# adapter-cast.net
KiCad netlist of a schematic drawn in EAGLE
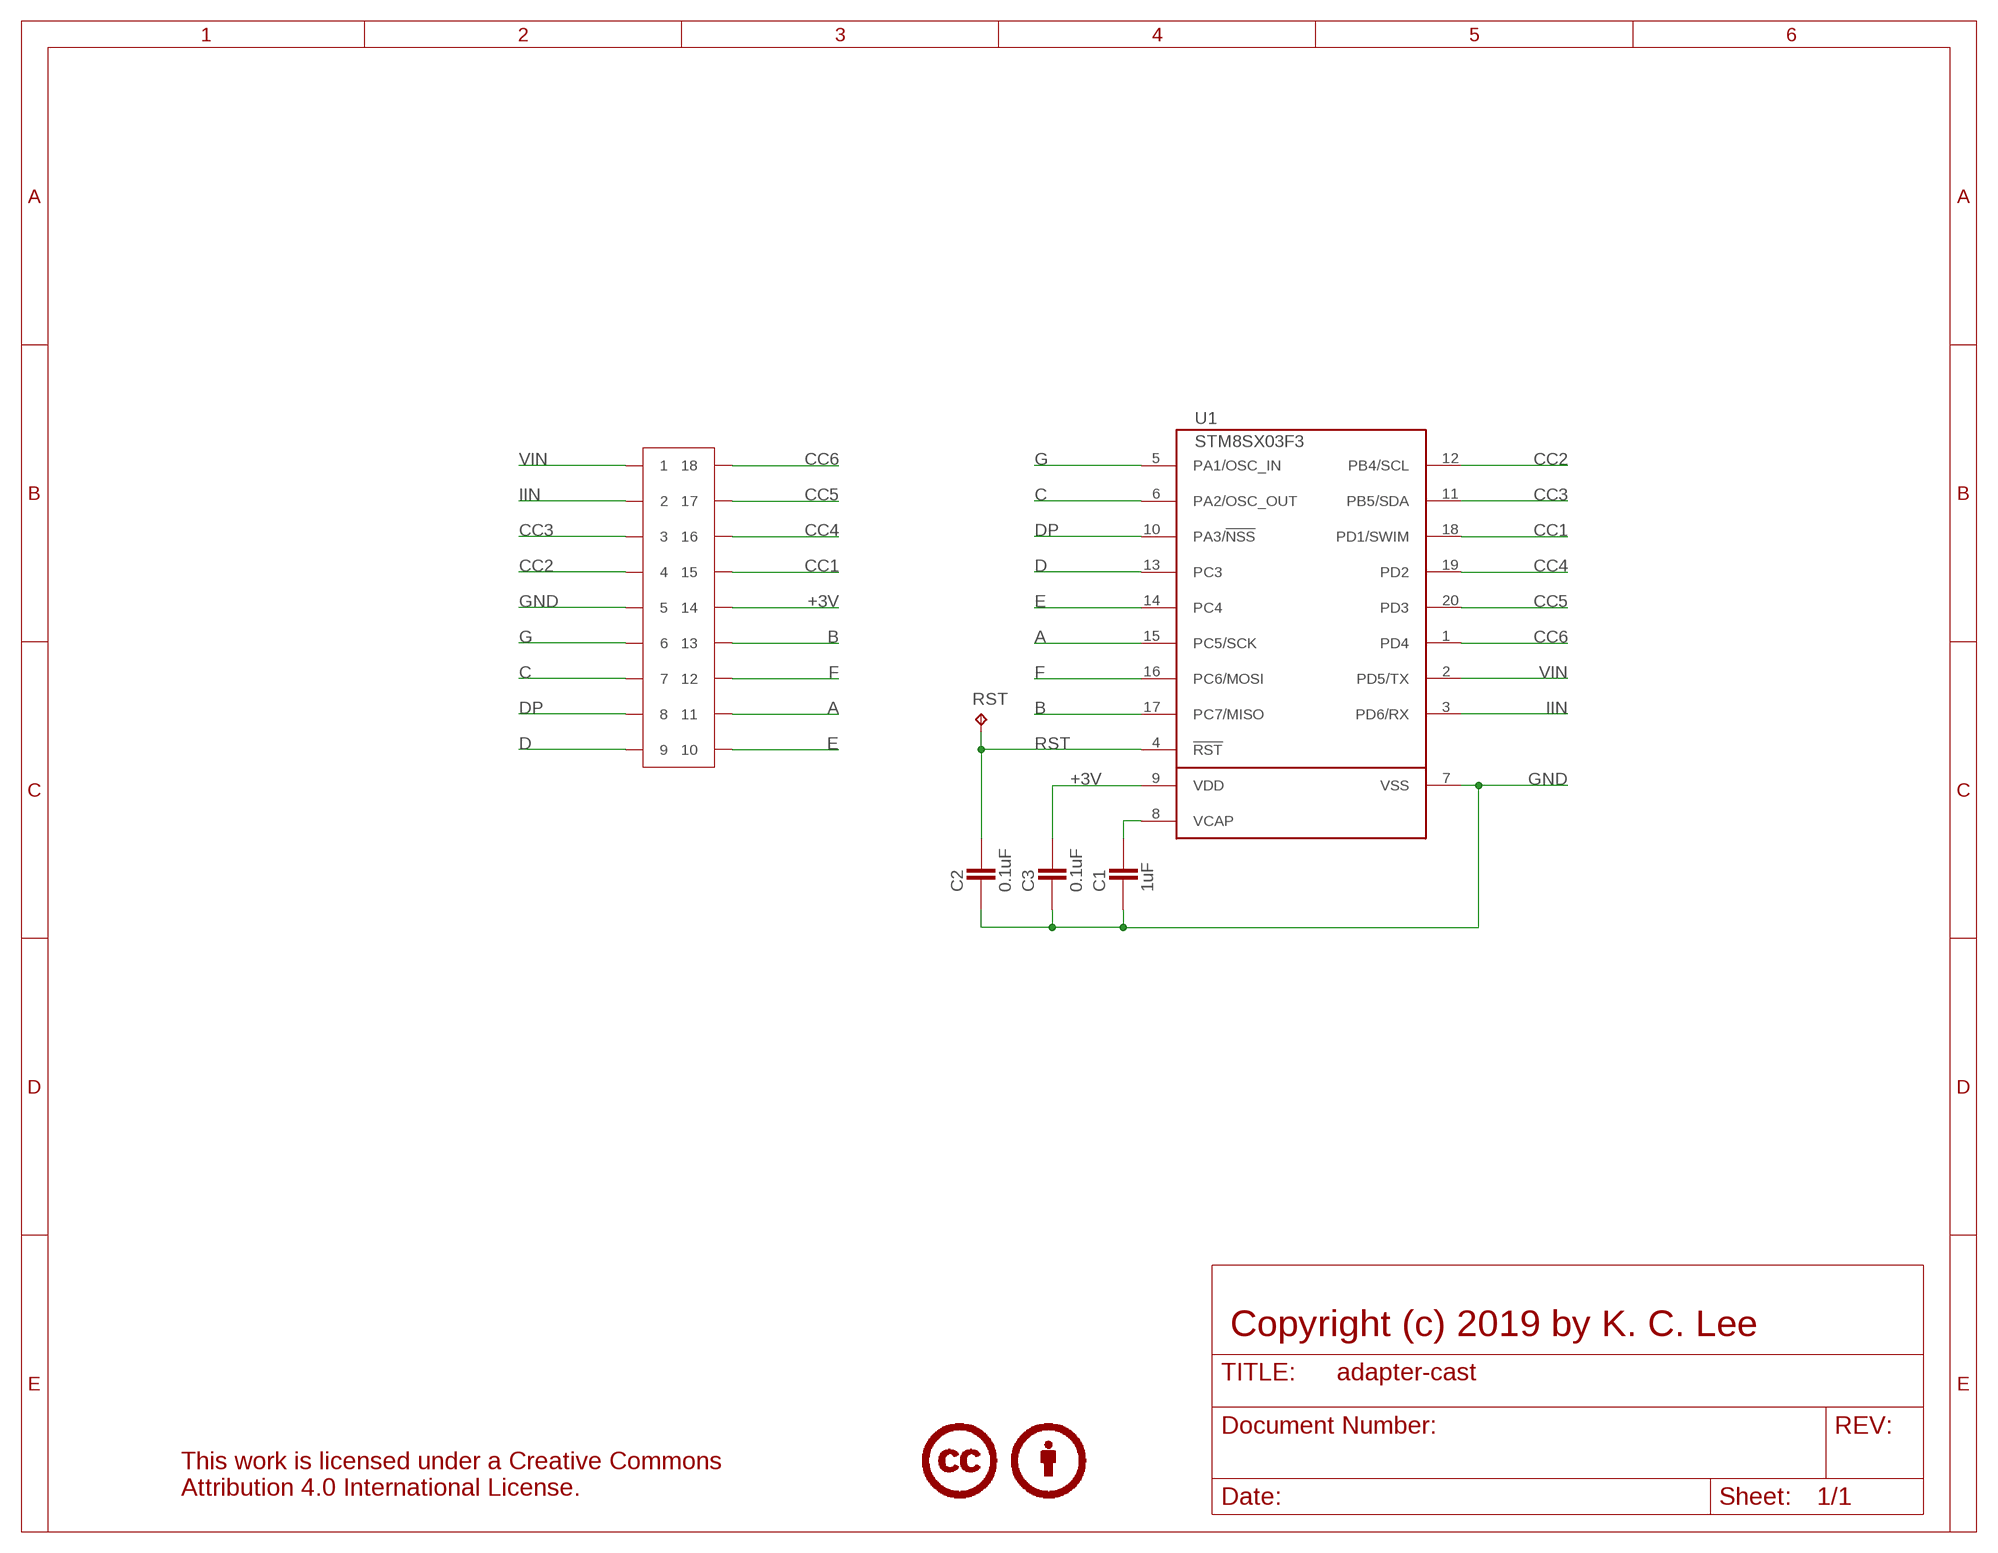
[diagram p0: schematic, sheet 1]

(export (version "E")
  (design (tool "Eeschema 10.0.6"))
  (components
    (comp (ref "C1")
      (value "1uF")
      (footprint "eagle-import:CAPC1608X92N")
      (libsource (lib "eagle-import") (part "CAPACITOR_0603"))
    )
    (comp (ref "C2")
      (value "0.1uF")
      (footprint "eagle-import:CAPC1608X92N")
      (libsource (lib "eagle-import") (part "CAPACITOR_0603"))
    )
    (comp (ref "C3")
      (value "0.1uF")
      (footprint "eagle-import:CAPC1608X92N")
      (libsource (lib "eagle-import") (part "CAPACITOR_0603"))
    )
    (comp (ref "LICENSE1")
      (value "CC-BYNONE")
      (footprint "eagle-import:CC-NONE")
      (libsource (lib "eagle-import") (part "CC-BYNONE"))
    )
    (comp (ref "P1")
      (value "DUMMY-SO18WCAST")
      (footprint "eagle-import:SO18W-CAST")
      (libsource (lib "eagle-import") (part "DUMMY-SO18WCAST"))
    )
    (comp (ref "RST")
      (value "TP")
      (footprint "eagle-import:TP11SQ")
      (libsource (lib "eagle-import") (part "TPTP11SQ"))
    )
    (comp (ref "U1")
      (value "STM8SX03F3")
      (footprint "eagle-import:TSSOP20")
      (libsource (lib "eagle-import") (part "STM8SX03F3"))
    )
  )
  (nets
    (net (code "1") (name "/+3V") (class "Default")
      (node (ref "C3") (pin "2") (pinfunction "2_2") (pintype "passive"))
      (node (ref "P1") (pin "P$14") (pinfunction "14_P$14") (pintype "bidirectional"))
      (node (ref "U1") (pin "9") (pinfunction "VDD_9") (pintype "input"))
    )
    (net (code "2") (name "/A") (class "Default")
      (node (ref "P1") (pin "P$11") (pinfunction "11_P$11") (pintype "bidirectional"))
      (node (ref "U1") (pin "15") (pinfunction "PC5/SCK_15") (pintype "bidirectional"))
    )
    (net (code "3") (name "/B") (class "Default")
      (node (ref "P1") (pin "P$13") (pinfunction "13_P$13") (pintype "bidirectional"))
      (node (ref "U1") (pin "17") (pinfunction "PC7/MISO_17") (pintype "bidirectional"))
    )
    (net (code "4") (name "/C") (class "Default")
      (node (ref "P1") (pin "P$7") (pinfunction "7_P$7") (pintype "bidirectional"))
      (node (ref "U1") (pin "6") (pinfunction "PA2/OSC_OUT_6") (pintype "output"))
    )
    (net (code "5") (name "/CC1") (class "Default")
      (node (ref "P1") (pin "P$15") (pinfunction "15_P$15") (pintype "bidirectional"))
      (node (ref "U1") (pin "18") (pinfunction "PD1/SWIM_18") (pintype "input"))
    )
    (net (code "6") (name "/CC2") (class "Default")
      (node (ref "P1") (pin "P$4") (pinfunction "4_P$4") (pintype "bidirectional"))
      (node (ref "U1") (pin "12") (pinfunction "PB4/SCL_12") (pintype "bidirectional"))
    )
    (net (code "7") (name "/CC3") (class "Default")
      (node (ref "P1") (pin "P$3") (pinfunction "3_P$3") (pintype "bidirectional"))
      (node (ref "U1") (pin "11") (pinfunction "PB5/SDA_11") (pintype "bidirectional"))
    )
    (net (code "8") (name "/CC4") (class "Default")
      (node (ref "P1") (pin "P$16") (pinfunction "16_P$16") (pintype "bidirectional"))
      (node (ref "U1") (pin "19") (pinfunction "PD2_19") (pintype "bidirectional"))
    )
    (net (code "9") (name "/CC5") (class "Default")
      (node (ref "P1") (pin "P$17") (pinfunction "17_P$17") (pintype "bidirectional"))
      (node (ref "U1") (pin "20") (pinfunction "PD3_20") (pintype "bidirectional"))
    )
    (net (code "10") (name "/CC6") (class "Default")
      (node (ref "P1") (pin "P$18") (pinfunction "18_P$18") (pintype "bidirectional"))
      (node (ref "U1") (pin "1") (pinfunction "PD4_1") (pintype "bidirectional"))
    )
    (net (code "11") (name "/D") (class "Default")
      (node (ref "P1") (pin "P$9") (pinfunction "9_P$9") (pintype "bidirectional"))
      (node (ref "U1") (pin "13") (pinfunction "PC3_13") (pintype "bidirectional"))
    )
    (net (code "12") (name "/DP") (class "Default")
      (node (ref "P1") (pin "P$8") (pinfunction "8_P$8") (pintype "bidirectional"))
      (node (ref "U1") (pin "10") (pinfunction "PA3/~{NSS}_10") (pintype "bidirectional"))
    )
    (net (code "13") (name "/E") (class "Default")
      (node (ref "P1") (pin "P$10") (pinfunction "10_P$10") (pintype "bidirectional"))
      (node (ref "U1") (pin "14") (pinfunction "PC4_14") (pintype "bidirectional"))
    )
    (net (code "14") (name "/F") (class "Default")
      (node (ref "P1") (pin "P$12") (pinfunction "12_P$12") (pintype "bidirectional"))
      (node (ref "U1") (pin "16") (pinfunction "PC6/MOSI_16") (pintype "bidirectional"))
    )
    (net (code "15") (name "/G") (class "Default")
      (node (ref "P1") (pin "P$6") (pinfunction "6_P$6") (pintype "bidirectional"))
      (node (ref "U1") (pin "5") (pinfunction "PA1/OSC_IN_5") (pintype "input"))
    )
    (net (code "16") (name "/GND") (class "Default")
      (node (ref "C1") (pin "1") (pinfunction "1_1") (pintype "passive"))
      (node (ref "C2") (pin "1") (pinfunction "1_1") (pintype "passive"))
      (node (ref "C3") (pin "1") (pinfunction "1_1") (pintype "passive"))
      (node (ref "P1") (pin "P$5") (pinfunction "5_P$5") (pintype "bidirectional"))
      (node (ref "U1") (pin "7") (pinfunction "VSS_7") (pintype "input"))
    )
    (net (code "17") (name "/IIN") (class "Default")
      (node (ref "P1") (pin "P$2") (pinfunction "2_P$2") (pintype "bidirectional"))
      (node (ref "U1") (pin "3") (pinfunction "PD6/RX_3") (pintype "bidirectional"))
    )
    (net (code "18") (name "/RST") (class "Default")
      (node (ref "C2") (pin "2") (pinfunction "2_2") (pintype "passive"))
      (node (ref "RST") (pin "TP") (pinfunction "TP_TP") (pintype "input"))
      (node (ref "U1") (pin "4") (pinfunction "~{RST}_4") (pintype "input"))
    )
    (net (code "19") (name "/VIN") (class "Default")
      (node (ref "P1") (pin "P$1") (pinfunction "1_P$1") (pintype "bidirectional"))
      (node (ref "U1") (pin "2") (pinfunction "PD5/TX_2") (pintype "bidirectional"))
    )
    (net (code "20") (name "Net-(U1-VCAP)") (class "Default")
      (node (ref "C1") (pin "2") (pinfunction "2_2") (pintype "passive"))
      (node (ref "U1") (pin "8") (pinfunction "VCAP_8") (pintype "input"))
    )
  )
)
